# RGB_Plugin_Board.net
KiCad netlist of a schematic drawn in Altium Designer
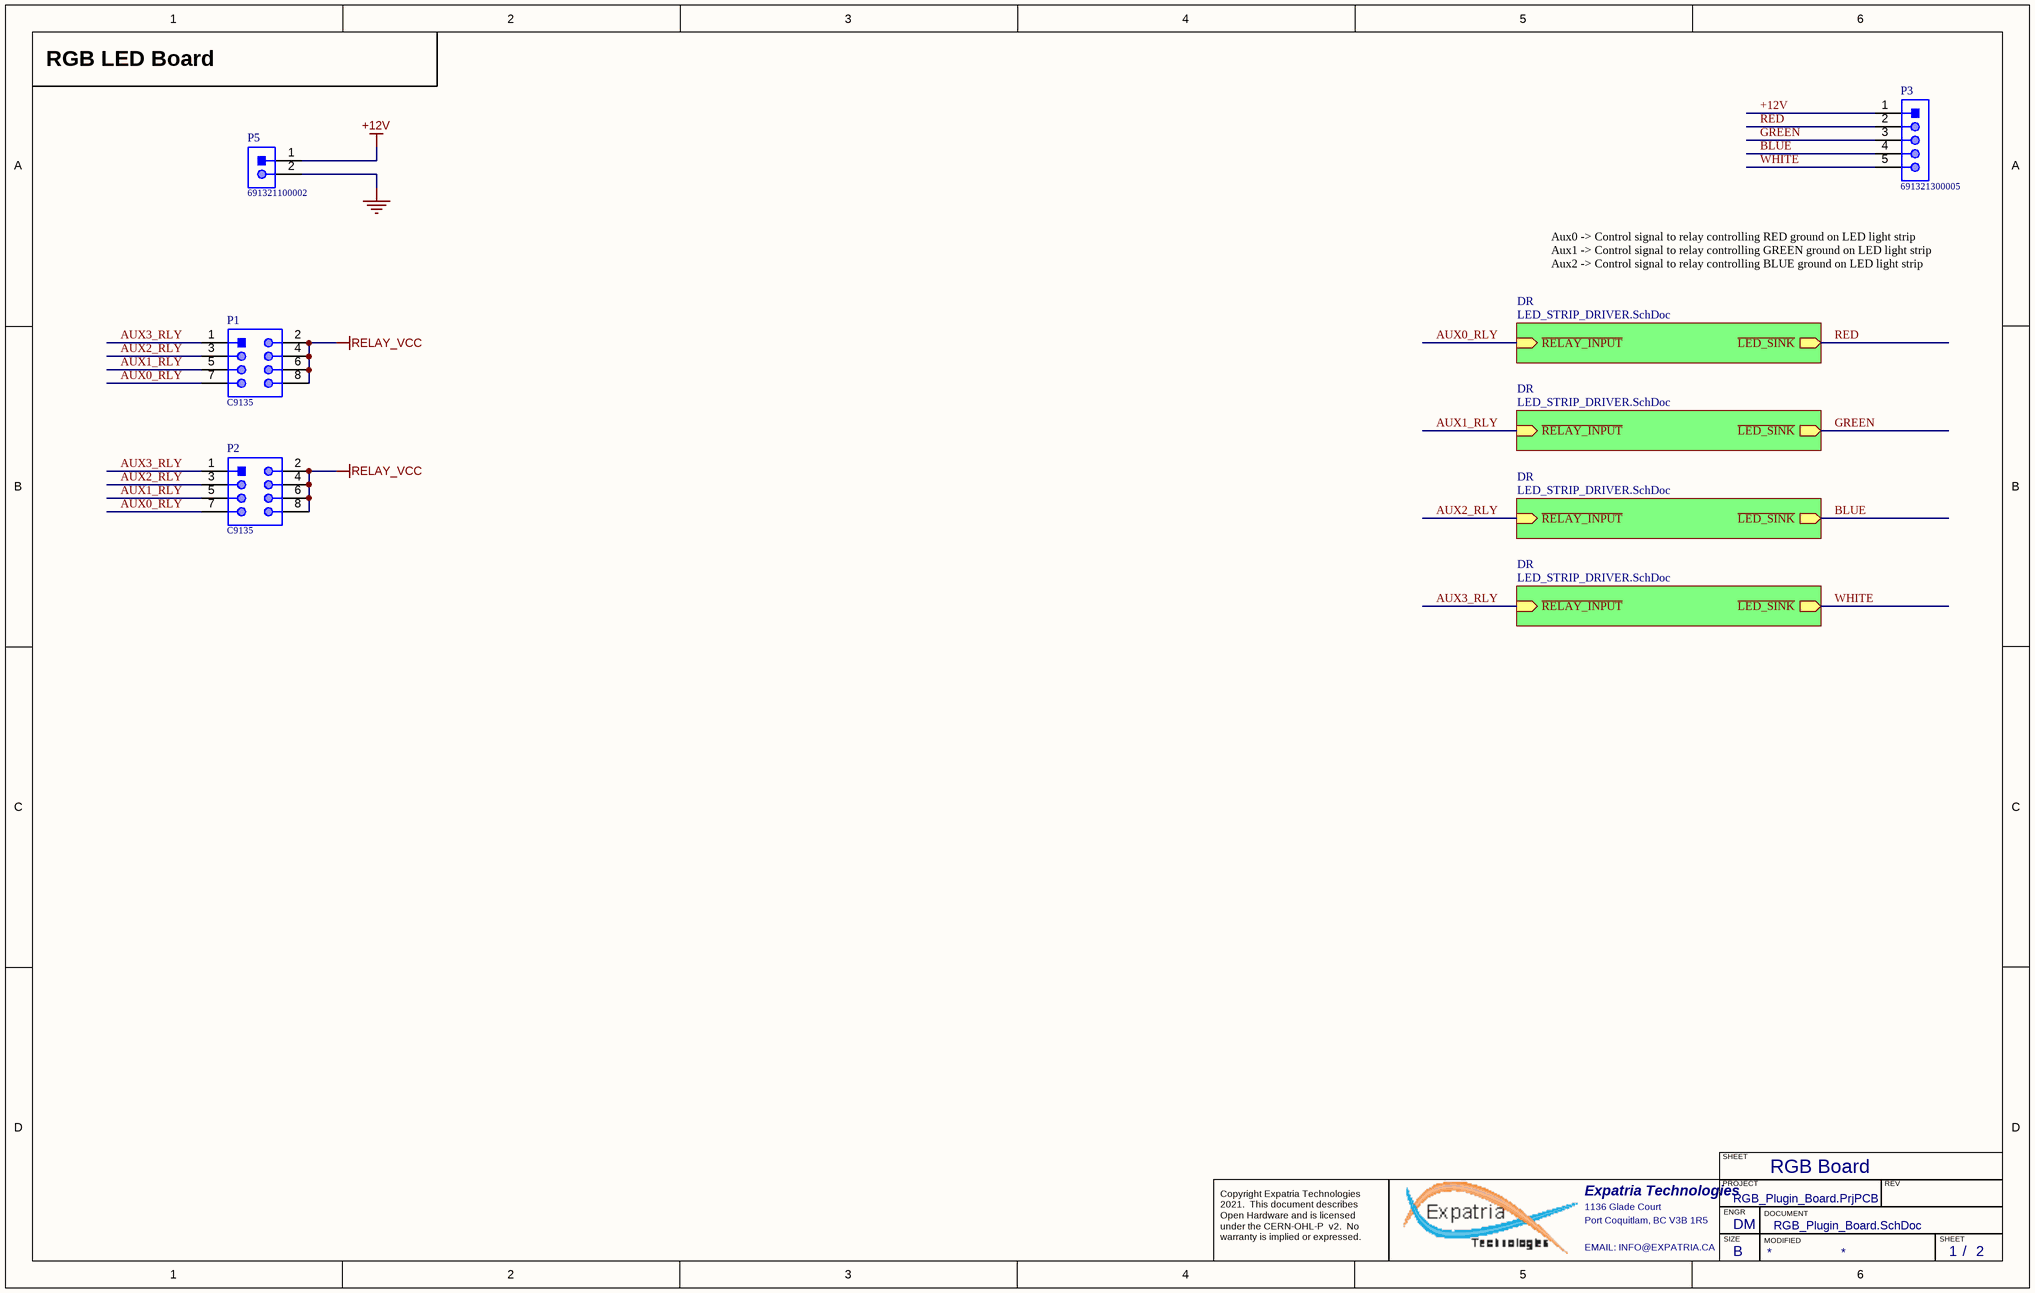
[diagram p0: RGB_Plugin_Board.SchDoc]

(export (version "E")
  (design (tool "Eeschema 10.0.6"))
  (components
    (comp (ref "P1")
      (value "C9135")
      (footprint "61200821621")
      (description "Male Box Header WR-BHD, THT, Vertical, pitch 2.54 mm, 8 pins")
      (fields (field (name "MANUFACTURER") "Wurth Elektronik") (field (name "PUBLISHER") "WurthElektronik"))
      (libsource (lib "PrintNC_GRBLHAL_Breakout") (part "WE-CN-2P-M-R8"))
    )
    (comp (ref "P2")
      (value "C9135")
      (footprint "61200821621")
      (description "Male Box Header WR-BHD, THT, Vertical, pitch 2.54 mm, 8 pins")
      (fields (field (name "MANUFACTURER") "Wurth Elektronik") (field (name "PUBLISHER") "WurthElektronik"))
      (libsource (lib "PrintNC_GRBLHAL_Breakout") (part "WE-CN-2P-M-R8"))
    )
    (comp (ref "P3")
      (value "691321300005")
      (footprint "691321300005")
      (description "Serie 321 - 3.81mm Vertical PCB Header WR-TBL, 5 pin")
      (fields (field (name "MANUFACTURER") "Wurth Elektronik") (field (name "PUBLISHER") "WurthElektronik"))
      (libsource (lib "Altium Content Vault") (part "WE-CN-1P-M-R5"))
    )
    (comp (ref "P5")
      (value "691321100002")
      (footprint "691321100002")
      (description "Serie 3211 - 3.50mm Vertical PCB Header WR-TBL, 2 pin")
      (fields (field (name "MANUFACTURER") "Wurth Elektronik") (field (name "PUBLISHER") "WurthElektronik"))
      (libsource (lib "Altium Content Vault") (part "WE-CN-1P-M-R2"))
    )
  )
  (nets
    (net (code "1") (name "+12V") (class "Default")
      (node (ref "P3") (pin "1") (pinfunction "1_1") (pintype "passive"))
      (node (ref "P5") (pin "1") (pinfunction "1_1") (pintype "passive"))
    )
    (net (code "2") (name "/AUX0_RLY") (class "Default")
      (node (ref "P1") (pin "7") (pinfunction "7_7") (pintype "passive"))
      (node (ref "P2") (pin "7") (pinfunction "7_7") (pintype "passive"))
    )
    (net (code "3") (name "/AUX1_RLY") (class "Default")
      (node (ref "P1") (pin "5") (pinfunction "5_5") (pintype "passive"))
      (node (ref "P2") (pin "5") (pinfunction "5_5") (pintype "passive"))
    )
    (net (code "4") (name "/AUX2_RLY") (class "Default")
      (node (ref "P1") (pin "3") (pinfunction "3_3") (pintype "passive"))
      (node (ref "P2") (pin "3") (pinfunction "3_3") (pintype "passive"))
    )
    (net (code "5") (name "/AUX3_RLY") (class "Default")
      (node (ref "P1") (pin "1") (pinfunction "1_1") (pintype "passive"))
      (node (ref "P2") (pin "1") (pinfunction "1_1") (pintype "passive"))
    )
    (net (code "6") (name "/BLUE") (class "Default")
      (node (ref "P3") (pin "4") (pinfunction "4_4") (pintype "passive"))
    )
    (net (code "7") (name "/GREEN") (class "Default")
      (node (ref "P3") (pin "3") (pinfunction "3_3") (pintype "passive"))
    )
    (net (code "8") (name "/RED") (class "Default")
      (node (ref "P3") (pin "2") (pinfunction "2_2") (pintype "passive"))
    )
    (net (code "9") (name "/WHITE") (class "Default")
      (node (ref "P3") (pin "5") (pinfunction "5_5") (pintype "passive"))
    )
    (net (code "10") (name "GND") (class "Default")
      (node (ref "P5") (pin "2") (pinfunction "2_2") (pintype "passive"))
    )
    (net (code "11") (name "RELAY_VCC") (class "Default")
      (node (ref "P1") (pin "2") (pinfunction "2_2") (pintype "passive"))
      (node (ref "P1") (pin "4") (pinfunction "4_4") (pintype "passive"))
      (node (ref "P1") (pin "6") (pinfunction "6_6") (pintype "passive"))
      (node (ref "P1") (pin "8") (pinfunction "8_8") (pintype "passive"))
      (node (ref "P2") (pin "2") (pinfunction "2_2") (pintype "passive"))
      (node (ref "P2") (pin "4") (pinfunction "4_4") (pintype "passive"))
      (node (ref "P2") (pin "6") (pinfunction "6_6") (pintype "passive"))
      (node (ref "P2") (pin "8") (pinfunction "8_8") (pintype "passive"))
    )
  )
)
